# PAYL0010_GMSK_Modem_wo_Proto.net
KiCad netlist of a schematic drawn in Altium Designer
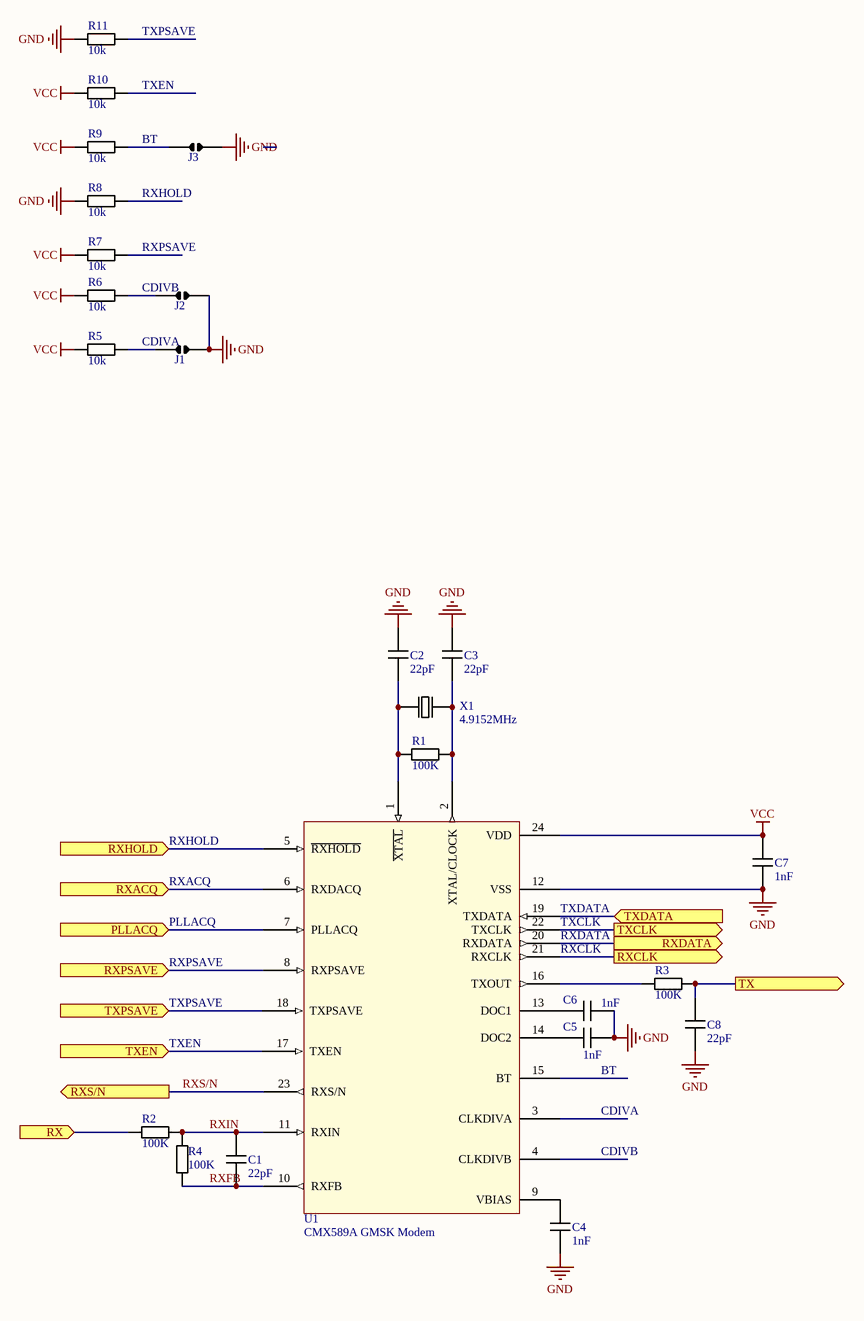
[diagram p0: PAYL0010 GMSK Modem wo Proto.SchDoc]

(export (version "E")
  (design (tool "Eeschema 10.0.6"))
  (components
    (comp (ref "C1")
      (value "22pF")
      (footprint "0805 Cap")
      (description "0805 MLCC - NP0, 5%")
      (fields (field (name "Comment") "0805 Cap"))
      (libsource (lib "GMSK Prototyping Board") (part "0805 MLCC - NP0, 5%"))
    )
    (comp (ref "C2")
      (value "22pF")
      (footprint "0805 Cap")
      (description "0805 MLCC - NP0, 5%")
      (fields (field (name "Comment") "0805 Cap"))
      (libsource (lib "GMSK Prototyping Board") (part "0805 MLCC - NP0, 5%"))
    )
    (comp (ref "C3")
      (value "22pF")
      (footprint "0805 Cap")
      (description "0805 MLCC - NP0, 5%")
      (fields (field (name "Comment") "0805 Cap"))
      (libsource (lib "GMSK Prototyping Board") (part "0805 MLCC - NP0, 5%"))
    )
    (comp (ref "C4")
      (value "1nF")
      (footprint "0805 Cap")
      (description "0805 MLCC - X7R, 10%")
      (fields (field (name "Comment") "0805 Cap"))
      (libsource (lib "GMSK Prototyping Board") (part "0805 MLCC - X7R, 10%"))
    )
    (comp (ref "C5")
      (value "1nF")
      (footprint "0805 Cap")
      (description "0805 MLCC - X7R, 10%")
      (fields (field (name "Comment") "0805 Cap"))
      (libsource (lib "GMSK Prototyping Board") (part "0805 MLCC - X7R, 10%"))
    )
    (comp (ref "C6")
      (value "1nF")
      (footprint "0805 Cap")
      (description "0805 MLCC - X7R, 10%")
      (fields (field (name "Comment") "0805 Cap"))
      (libsource (lib "GMSK Prototyping Board") (part "0805 MLCC - X7R, 10%"))
    )
    (comp (ref "C7")
      (value "1nF")
      (footprint "0805 Cap")
      (description "0805 MLCC - X7R, 10%")
      (fields (field (name "Comment") "0805 Cap"))
      (libsource (lib "GMSK Prototyping Board") (part "0805 MLCC - X7R, 10%"))
    )
    (comp (ref "C8")
      (value "22pF")
      (footprint "0805 Cap")
      (description "0805 MLCC - NP0, 5%")
      (fields (field (name "Comment") "0805 Cap"))
      (libsource (lib "GMSK Prototyping Board") (part "0805 MLCC - NP0, 5%"))
    )
    (comp (ref "J1")
      (value "Jumper")
      (footprint "Solder Jumper C")
      (description "Solder Bridge")
      (libsource (lib "GMSK Prototyping Board") (part "Solder Bridge"))
    )
    (comp (ref "J2")
      (value "Jumper")
      (footprint "Solder Jumper C")
      (description "Solder Bridge")
      (libsource (lib "GMSK Prototyping Board") (part "Solder Bridge"))
    )
    (comp (ref "J3")
      (value "Jumper")
      (footprint "Solder Jumper C")
      (description "Solder Bridge")
      (libsource (lib "GMSK Prototyping Board") (part "Solder Bridge"))
    )
    (comp (ref "R1")
      (value "100K")
      (footprint "0805 Resistor")
      (description "0805 Thin Film Resistor 0.1%")
      (fields (field (name "Comment") "0805 Resistor"))
      (libsource (lib "GMSK Prototyping Board") (part "0805 Thin Film Resistor 0.1%"))
    )
    (comp (ref "R2")
      (value "100K")
      (footprint "0805 Resistor")
      (description "0805 Thin Film Resistor 0.1%")
      (fields (field (name "Comment") "0805 Resistor"))
      (libsource (lib "GMSK Prototyping Board") (part "0805 Thin Film Resistor 0.1%"))
    )
    (comp (ref "R3")
      (value "100K")
      (footprint "0805 Resistor")
      (description "0805 Thin Film Resistor 0.1%")
      (fields (field (name "Comment") "0805 Resistor"))
      (libsource (lib "GMSK Prototyping Board") (part "0805 Thin Film Resistor 0.1%"))
    )
    (comp (ref "R4")
      (value "100K")
      (footprint "0805 Resistor")
      (description "0805 Thin Film Resistor 0.1%")
      (fields (field (name "Comment") "0805 Resistor"))
      (libsource (lib "") (part "0805 Thin Film Resistor 0.1%_2"))
    )
    (comp (ref "R5")
      (value "10k")
      (footprint "0805 Resistor")
      (description "0805 Thin Film Resistor 0.1%")
      (fields (field (name "Comment") "0805 Resistor"))
      (libsource (lib "") (part "0805 Thin Film Resistor 0.1%_1"))
    )
    (comp (ref "R6")
      (value "10k")
      (footprint "0805 Resistor")
      (description "0805 Thin Film Resistor 0.1%")
      (fields (field (name "Comment") "0805 Resistor"))
      (libsource (lib "") (part "0805 Thin Film Resistor 0.1%_1"))
    )
    (comp (ref "R7")
      (value "10k")
      (footprint "0805 Resistor")
      (description "0805 Thin Film Resistor 0.1%")
      (fields (field (name "Comment") "0805 Resistor"))
      (libsource (lib "") (part "0805 Thin Film Resistor 0.1%_1"))
    )
    (comp (ref "R8")
      (value "10k")
      (footprint "0805 Resistor")
      (description "0805 Thin Film Resistor 0.1%")
      (fields (field (name "Comment") "0805 Resistor"))
      (libsource (lib "") (part "0805 Thin Film Resistor 0.1%_1"))
    )
    (comp (ref "R9")
      (value "10k")
      (footprint "0805 Resistor")
      (description "0805 Thin Film Resistor 0.1%")
      (fields (field (name "Comment") "0805 Resistor"))
      (libsource (lib "") (part "0805 Thin Film Resistor 0.1%_1"))
    )
    (comp (ref "R10")
      (value "10k")
      (footprint "0805 Resistor")
      (description "0805 Thin Film Resistor 0.1%")
      (fields (field (name "Comment") "0805 Resistor"))
      (libsource (lib "") (part "0805 Thin Film Resistor 0.1%_1"))
    )
    (comp (ref "R11")
      (value "10k")
      (footprint "0805 Resistor")
      (description "0805 Thin Film Resistor 0.1%")
      (fields (field (name "Comment") "0805 Resistor"))
      (libsource (lib "") (part "0805 Thin Film Resistor 0.1%_1"))
    )
    (comp (ref "U1")
      (value "CMX589A GMSK Modem")
      (footprint "SOIC24 - GMSK MODEM")
      (libsource (lib "GMSK Prototyping Board") (part "CMX589A"))
    )
    (comp (ref "X1")
      (value "4.9152MHz")
      (footprint "HC49")
      (description "HC49 Crystal")
      (libsource (lib "GMSK Prototyping Board") (part "HC49 Crystal"))
    )
  )
  (nets
    (net (code "1") (name "/BT") (class "Default")
      (node (ref "J3") (pin "1") (pinfunction "1_1") (pintype "passive"))
      (node (ref "R9") (pin "1") (pinfunction "1_1") (pintype "passive"))
      (node (ref "U1") (pin "15") (pinfunction "BT_15") (pintype "passive"))
    )
    (net (code "2") (name "/CDIVA") (class "Default")
      (node (ref "J1") (pin "2") (pinfunction "2_2") (pintype "passive"))
      (node (ref "R5") (pin "1") (pinfunction "1_1") (pintype "passive"))
      (node (ref "U1") (pin "3") (pinfunction "CLKDIVA_3") (pintype "passive"))
    )
    (net (code "3") (name "/CDIVB") (class "Default")
      (node (ref "J2") (pin "1") (pinfunction "1_1") (pintype "passive"))
      (node (ref "R6") (pin "1") (pinfunction "1_1") (pintype "passive"))
      (node (ref "U1") (pin "4") (pinfunction "CLKDIVB_4") (pintype "passive"))
    )
    (net (code "4") (name "/PLLACQ") (class "Default")
      (node (ref "U1") (pin "7") (pinfunction "PLLACQ_7") (pintype "input"))
    )
    (net (code "5") (name "/RX") (class "Default")
      (node (ref "R2") (pin "1") (pinfunction "1_1") (pintype "passive"))
    )
    (net (code "6") (name "/RXACQ") (class "Default")
      (node (ref "U1") (pin "6") (pinfunction "RXDACQ_6") (pintype "input"))
    )
    (net (code "7") (name "/RXCLK") (class "Default")
      (node (ref "U1") (pin "21") (pinfunction "RXCLK_21") (pintype "output"))
    )
    (net (code "8") (name "/RXDATA") (class "Default")
      (node (ref "U1") (pin "20") (pinfunction "RXDATA_20") (pintype "output"))
    )
    (net (code "9") (name "/RXFB") (class "Default")
      (node (ref "C1") (pin "1") (pinfunction "1_1") (pintype "passive"))
      (node (ref "R4") (pin "2") (pinfunction "2_2") (pintype "passive"))
      (node (ref "U1") (pin "10") (pinfunction "RXFB_10") (pintype "output"))
    )
    (net (code "10") (name "/RXHOLD") (class "Default")
      (node (ref "R8") (pin "1") (pinfunction "1_1") (pintype "passive"))
      (node (ref "U1") (pin "5") (pinfunction "~{RXHOLD}_5") (pintype "input"))
    )
    (net (code "11") (name "/RXIN") (class "Default")
      (node (ref "C1") (pin "2") (pinfunction "2_2") (pintype "passive"))
      (node (ref "R2") (pin "2") (pinfunction "2_2") (pintype "passive"))
      (node (ref "R4") (pin "1") (pinfunction "1_1") (pintype "passive"))
      (node (ref "U1") (pin "11") (pinfunction "RXIN_11") (pintype "input"))
    )
    (net (code "12") (name "/RXPSAVE") (class "Default")
      (node (ref "R7") (pin "1") (pinfunction "1_1") (pintype "passive"))
      (node (ref "U1") (pin "8") (pinfunction "RXPSAVE_8") (pintype "input"))
    )
    (net (code "13") (name "/RXS{slash}N") (class "Default")
      (node (ref "U1") (pin "23") (pinfunction "RXS/N_23") (pintype "output"))
    )
    (net (code "14") (name "/TX") (class "Default")
      (node (ref "C8") (pin "1") (pinfunction "1_1") (pintype "passive"))
      (node (ref "R3") (pin "2") (pinfunction "2_2") (pintype "passive"))
    )
    (net (code "15") (name "/TXCLK") (class "Default")
      (node (ref "U1") (pin "22") (pinfunction "TXCLK_22") (pintype "output"))
    )
    (net (code "16") (name "/TXDATA") (class "Default")
      (node (ref "U1") (pin "19") (pinfunction "TXDATA_19") (pintype "input"))
    )
    (net (code "17") (name "/TXEN") (class "Default")
      (node (ref "R10") (pin "1") (pinfunction "1_1") (pintype "passive"))
      (node (ref "U1") (pin "17") (pinfunction "TXEN_17") (pintype "input"))
    )
    (net (code "18") (name "/TXPSAVE") (class "Default")
      (node (ref "R11") (pin "1") (pinfunction "1_1") (pintype "passive"))
      (node (ref "U1") (pin "18") (pinfunction "TXPSAVE_18") (pintype "input"))
    )
    (net (code "19") (name "GND") (class "Default")
      (node (ref "C2") (pin "2") (pinfunction "2_2") (pintype "passive"))
      (node (ref "C3") (pin "2") (pinfunction "2_2") (pintype "passive"))
      (node (ref "C4") (pin "2") (pinfunction "2_2") (pintype "passive"))
      (node (ref "C5") (pin "2") (pinfunction "2_2") (pintype "passive"))
      (node (ref "C6") (pin "1") (pinfunction "1_1") (pintype "passive"))
      (node (ref "C7") (pin "2") (pinfunction "2_2") (pintype "passive"))
      (node (ref "C8") (pin "2") (pinfunction "2_2") (pintype "passive"))
      (node (ref "J1") (pin "1") (pinfunction "1_1") (pintype "passive"))
      (node (ref "J2") (pin "2") (pinfunction "2_2") (pintype "passive"))
      (node (ref "J3") (pin "2") (pinfunction "2_2") (pintype "passive"))
      (node (ref "R11") (pin "2") (pinfunction "2_2") (pintype "passive"))
      (node (ref "R8") (pin "2") (pinfunction "2_2") (pintype "passive"))
      (node (ref "U1") (pin "12") (pinfunction "VSS_12") (pintype "power_in"))
    )
    (net (code "20") (name "Net-(U1-DOC1)") (class "Default")
      (node (ref "C6") (pin "2") (pinfunction "2_2") (pintype "passive"))
      (node (ref "U1") (pin "13") (pinfunction "DOC1_13") (pintype "passive"))
    )
    (net (code "21") (name "Net-(U1-DOC2)") (class "Default")
      (node (ref "C5") (pin "1") (pinfunction "1_1") (pintype "passive"))
      (node (ref "U1") (pin "14") (pinfunction "DOC2_14") (pintype "passive"))
    )
    (net (code "22") (name "Net-(U1-TXOUT)") (class "Default")
      (node (ref "R3") (pin "1") (pinfunction "1_1") (pintype "passive"))
      (node (ref "U1") (pin "16") (pinfunction "TXOUT_16") (pintype "output"))
    )
    (net (code "23") (name "Net-(U1-VBIAS)") (class "Default")
      (node (ref "C4") (pin "1") (pinfunction "1_1") (pintype "passive"))
      (node (ref "U1") (pin "9") (pinfunction "VBIAS_9") (pintype "passive"))
    )
    (net (code "24") (name "Net-(U1-XTAL{slash}CLOCK)") (class "Default")
      (node (ref "C3") (pin "1") (pinfunction "1_1") (pintype "passive"))
      (node (ref "R1") (pin "2") (pinfunction "2_2") (pintype "passive"))
      (node (ref "U1") (pin "2") (pinfunction "XTAL/CLOCK_2") (pintype "output"))
      (node (ref "X1") (pin "2") (pinfunction "2_2") (pintype "passive"))
    )
    (net (code "25") (name "Net-(U1-~{XTAL})") (class "Default")
      (node (ref "C2") (pin "1") (pinfunction "1_1") (pintype "passive"))
      (node (ref "R1") (pin "1") (pinfunction "1_1") (pintype "passive"))
      (node (ref "U1") (pin "1") (pinfunction "~{XTAL}_1") (pintype "input"))
      (node (ref "X1") (pin "1") (pinfunction "1_1") (pintype "passive"))
    )
    (net (code "26") (name "VCC") (class "Default")
      (node (ref "C7") (pin "1") (pinfunction "1_1") (pintype "passive"))
      (node (ref "R10") (pin "2") (pinfunction "2_2") (pintype "passive"))
      (node (ref "R5") (pin "2") (pinfunction "2_2") (pintype "passive"))
      (node (ref "R6") (pin "2") (pinfunction "2_2") (pintype "passive"))
      (node (ref "R7") (pin "2") (pinfunction "2_2") (pintype "passive"))
      (node (ref "R9") (pin "2") (pinfunction "2_2") (pintype "passive"))
      (node (ref "U1") (pin "24") (pinfunction "VDD_24") (pintype "power_in"))
    )
  )
)
